# Flyback_Controller.net
KiCad netlist of a schematic drawn in Altium Designer
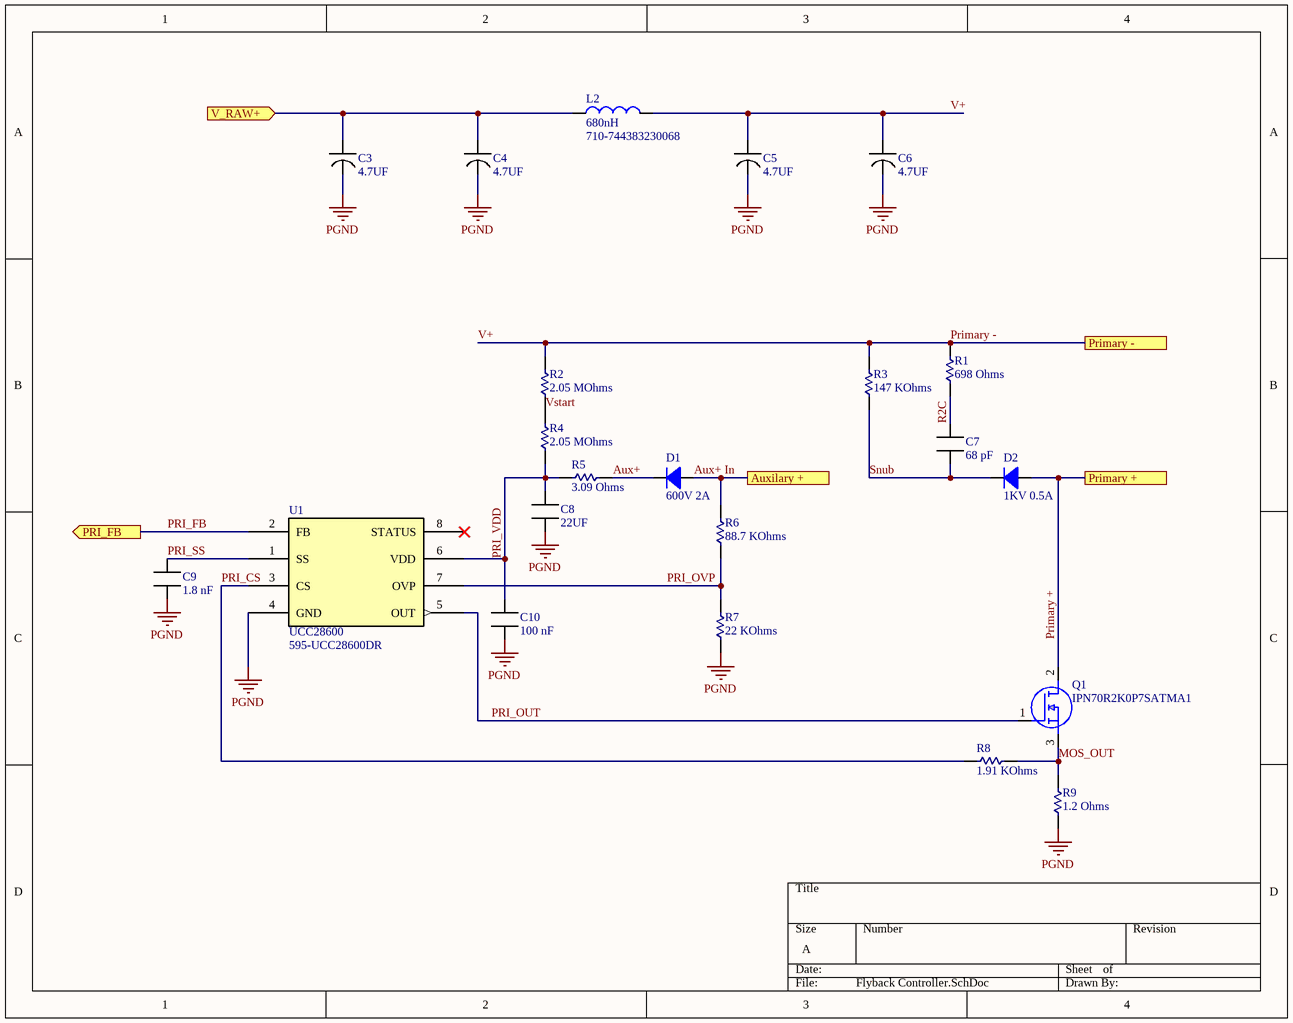
[diagram p0: Flyback Controller.SchDoc]

(export (version "E")
  (design (tool "Eeschema 10.0.6"))
  (components
    (comp (ref "C3")
      (value "4.7UF")
      (footprint "Alum Radial Cap 5mm")
      (description "Aluminum Electrolytic Capacitors - Radial Leaded 400V 4.7uF 20% 1000Hrs")
      (libsource (lib "SMPS Schlib") (part "ESE475M400AH9AA"))
    )
    (comp (ref "C4")
      (value "4.7UF")
      (footprint "Alum Radial Cap 5mm")
      (description "Aluminum Electrolytic Capacitors - Radial Leaded 400V 4.7uF 20% 1000Hrs")
      (libsource (lib "SMPS Schlib") (part "ESE475M400AH9AA"))
    )
    (comp (ref "C5")
      (value "4.7UF")
      (footprint "Alum Radial Cap 5mm")
      (description "Aluminum Electrolytic Capacitors - Radial Leaded 400V 4.7uF 20% 1000Hrs")
      (libsource (lib "SMPS Schlib") (part "ESE475M400AH9AA"))
    )
    (comp (ref "C6")
      (value "4.7UF")
      (footprint "Alum Radial Cap 5mm")
      (description "Aluminum Electrolytic Capacitors - Radial Leaded 400V 4.7uF 20% 1000Hrs")
      (libsource (lib "SMPS Schlib") (part "ESE475M400AH9AA"))
    )
    (comp (ref "C7")
      (value "68 pF")
      (footprint "Cap 1206")
      (description "Multilayer Ceramic Capacitors MLCC - SMD/SMT 1k V 68 pF C0G 1206 5%")
      (libsource (lib "SMPS Schlib") (part "CC1206JKNPOCBN680"))
    )
    (comp (ref "C8")
      (value "22UF")
      (footprint "Res 0805")
      (description "Multilayer Ceramic Capacitors MLCC - SMD/SMT 22uF+/-20% 25V X5R 2 0805")
      (libsource (lib "SMPS Schlib") (part "CL21A226MAYNNNE"))
    )
    (comp (ref "C9")
      (value "1.8 nF")
      (footprint "Cap 0603")
      (description "Multilayer Ceramic Capacitors MLCC - SMD/SMT 0603 1800pF 50volts X7R 10%")
      (libsource (lib "SMPS Schlib") (part "VJ0603Y182KXACW1BC"))
    )
    (comp (ref "C10")
      (value "100 nF")
      (footprint "Cap 1206")
      (description "Multilayer Ceramic Capacitors MLCC - SMD/SMT CGA 1206 450V 0.1uF X7T 20% AEC-Q200")
      (libsource (lib "SMPS Schlib") (part "CGA5L4X7T2W104M160AA"))
    )
    (comp (ref "D1")
      (value "600V 2A")
      (footprint "FLAT_SMT")
      (description "Diodes - General Purpose, Power, Switching 600V 2A M-FLAT")
      (libsource (lib "SMPS Schlib") (part "CMF01(TE12L,Q,M)"))
    )
    (comp (ref "D2")
      (value "1KV 0.5A")
      (footprint "FLAT_SMT")
      (description "Rectifiers Super Fast Diode 1000V 0.5A 100ns")
      (libsource (lib "SMPS Schlib") (part "CMF05(TE12L,Q,M)"))
    )
    (comp (ref "L2")
      (value "680nH")
      (footprint "IND 1008")
      (description "Power Inductors - Leaded WE-MAPI 680nH 3.1A DCR=60mOhms AECQ200")
      (fields (field (name "SUPPLIER PART NUMBER 1") "710-744383230068"))
      (libsource (lib "SMPS Schlib") (part "744383230068"))
    )
    (comp (ref "Q1")
      (value "IPN70R2K0P7SATMA1")
      (footprint "SOT-223-3")
      (description "MOSFET CONSUMER 700V 3A 1.64Ohms")
      (libsource (lib "SMPS Schlib") (part "IPN70R2K0P7SATMA1"))
    )
    (comp (ref "R1")
      (value "698 Ohms")
      (footprint "Res 0805")
      (description "Thick Film Resistors - SMD 698 Ohms 125 mW 0805 1%")
      (libsource (lib "SMPS Schlib") (part "RC0805FR-07698RL"))
    )
    (comp (ref "R2")
      (value "2.05 MOhms")
      (footprint "RES 1206")
      (description "Thick Film Resistors - SMD 2.05 MOhms 250 mW 1206 1%")
      (libsource (lib "SMPS Schlib") (part "RC1206FR-072M05L"))
    )
    (comp (ref "R3")
      (value "147 KOhms")
      (footprint "Res 0805")
      (description "Thick Film Resistors - SMD 0805 147Kohms 0.5W 1% AEC-Q200")
      (libsource (lib "SMPS Schlib") (part "ERJ-P06F1473V"))
    )
    (comp (ref "R4")
      (value "2.05 MOhms")
      (footprint "RES 1206")
      (description "Thick Film Resistors - SMD 2.05 MOhms 250 mW 1206 1%")
      (libsource (lib "SMPS Schlib") (part "RC1206FR-072M05L"))
    )
    (comp (ref "R5")
      (value "3.09 Ohms")
      (footprint "Res 0805")
      (description "Thick Film Resistors - SMD 3.09Ohms 1/8W 0805 1%")
      (libsource (lib "SMPS Schlib") (part "RC0805FR-073R09L"))
    )
    (comp (ref "R6")
      (value "88.7 KOhms")
      (footprint "Res 0805")
      (description "Thin Film Resistors - SMD 0805 88.7Kohm 0.1% 25ppm")
      (libsource (lib "SMPS Schlib") (part "ERA-6AEB8872V"))
    )
    (comp (ref "R7")
      (value "22 KOhms")
      (footprint "Res 0805")
      (description "Thin Film Resistors - SMD 1/8W 22K ohm .1% 25ppm")
      (libsource (lib "SMPS Schlib") (part "RT0805BRD0722KL"))
    )
    (comp (ref "R8")
      (value "1.91 KOhms")
      (footprint "Res 0805")
      (description "Thick Film Resistors - SMD 1.91K 1%")
      (libsource (lib "SMPS Schlib") (part "CR0805-FX-1911ELF"))
    )
    (comp (ref "R9")
      (value "1.2 Ohms")
      (footprint "RES 1206")
      (description "Thick Film Resistors - SMD 1.2Ohms 1/4W 1206 1% AEC-Q200 Standard Power Version")
      (libsource (lib "SMPS Schlib") (part "AC1206FR-071R2L"))
    )
    (comp (ref "U1")
      (value "UCC28600")
      (footprint "UCC28600")
      (description "AC/DC Converters Quasi Res Flyback Green Mode Cntrlr")
      (fields (field (name "SUPPLIER PART NUMBER 1") "595-UCC28600DR"))
      (libsource (lib "SMPS Schlib") (part "UCC28600DR"))
    )
  )
  (nets
    (net (code "1") (name "/Aux+") (class "Default")
      (node (ref "D1") (pin "2") (pinfunction "2_2") (pintype "passive"))
      (node (ref "R5") (pin "2") (pinfunction "B_2") (pintype "passive"))
    )
    (net (code "2") (name "/Aux+ In") (class "Default")
      (node (ref "D1") (pin "1") (pinfunction "1_1") (pintype "passive"))
      (node (ref "R6") (pin "2") (pinfunction "B_2") (pintype "passive"))
    )
    (net (code "3") (name "/MOS_OUT") (class "Default")
      (node (ref "Q1") (pin "3") (pinfunction "S_3") (pintype "passive"))
      (node (ref "R8") (pin "2") (pinfunction "B_2") (pintype "passive"))
      (node (ref "R9") (pin "2") (pinfunction "B_2") (pintype "passive"))
    )
    (net (code "4") (name "/PRI_CS") (class "Default")
      (node (ref "R8") (pin "1") (pinfunction "A_1") (pintype "passive"))
      (node (ref "U1") (pin "3") (pinfunction "CS_3") (pintype "passive"))
    )
    (net (code "5") (name "/PRI_FB") (class "Default")
      (node (ref "U1") (pin "2") (pinfunction "FB_2") (pintype "passive"))
    )
    (net (code "6") (name "/PRI_OUT") (class "Default")
      (node (ref "Q1") (pin "1") (pinfunction "G_1") (pintype "passive"))
      (node (ref "U1") (pin "5") (pinfunction "OUT_5") (pintype "output"))
    )
    (net (code "7") (name "/PRI_OVP") (class "Default")
      (node (ref "R6") (pin "1") (pinfunction "A_1") (pintype "passive"))
      (node (ref "R7") (pin "2") (pinfunction "B_2") (pintype "passive"))
      (node (ref "U1") (pin "7") (pinfunction "OVP_7") (pintype "passive"))
    )
    (net (code "8") (name "/PRI_SS") (class "Default")
      (node (ref "C9") (pin "2") (pinfunction "2_2") (pintype "passive"))
      (node (ref "U1") (pin "1") (pinfunction "SS_1") (pintype "passive"))
    )
    (net (code "9") (name "/PRI_VDD") (class "Default")
      (node (ref "C10") (pin "2") (pinfunction "2_2") (pintype "passive"))
      (node (ref "C8") (pin "2") (pinfunction "2_2") (pintype "passive"))
      (node (ref "R4") (pin "1") (pinfunction "A_1") (pintype "passive"))
      (node (ref "R5") (pin "1") (pinfunction "A_1") (pintype "passive"))
      (node (ref "U1") (pin "6") (pinfunction "VDD_6") (pintype "power_in"))
    )
    (net (code "10") (name "/Primary +") (class "Default")
      (node (ref "D2") (pin "1") (pinfunction "1_1") (pintype "passive"))
      (node (ref "Q1") (pin "2") (pinfunction "D_2") (pintype "passive"))
    )
    (net (code "11") (name "/Primary -") (class "Default")
      (node (ref "C5") (pin "1") (pinfunction "1_1") (pintype "passive"))
      (node (ref "C6") (pin "1") (pinfunction "1_1") (pintype "passive"))
      (node (ref "L2") (pin "2") (pinfunction "2_2") (pintype "passive"))
      (node (ref "R1") (pin "2") (pinfunction "B_2") (pintype "passive"))
      (node (ref "R2") (pin "2") (pinfunction "B_2") (pintype "passive"))
      (node (ref "R3") (pin "2") (pinfunction "B_2") (pintype "passive"))
    )
    (net (code "12") (name "/R2C") (class "Default")
      (node (ref "C7") (pin "2") (pinfunction "2_2") (pintype "passive"))
      (node (ref "R1") (pin "1") (pinfunction "A_1") (pintype "passive"))
    )
    (net (code "13") (name "/Snub") (class "Default")
      (node (ref "C7") (pin "1") (pinfunction "1_1") (pintype "passive"))
      (node (ref "D2") (pin "2") (pinfunction "2_2") (pintype "passive"))
      (node (ref "R3") (pin "1") (pinfunction "A_1") (pintype "passive"))
    )
    (net (code "14") (name "/V_RAW+") (class "Default")
      (node (ref "C3") (pin "1") (pinfunction "1_1") (pintype "passive"))
      (node (ref "C4") (pin "1") (pinfunction "1_1") (pintype "passive"))
      (node (ref "L2") (pin "1") (pinfunction "1_1") (pintype "passive"))
    )
    (net (code "15") (name "/Vstart") (class "Default")
      (node (ref "R2") (pin "1") (pinfunction "A_1") (pintype "passive"))
      (node (ref "R4") (pin "2") (pinfunction "B_2") (pintype "passive"))
    )
    (net (code "16") (name "PGND") (class "Default")
      (node (ref "C10") (pin "1") (pinfunction "1_1") (pintype "passive"))
      (node (ref "C3") (pin "2") (pinfunction "2_2") (pintype "passive"))
      (node (ref "C4") (pin "2") (pinfunction "2_2") (pintype "passive"))
      (node (ref "C5") (pin "2") (pinfunction "2_2") (pintype "passive"))
      (node (ref "C6") (pin "2") (pinfunction "2_2") (pintype "passive"))
      (node (ref "C8") (pin "1") (pinfunction "1_1") (pintype "passive"))
      (node (ref "C9") (pin "1") (pinfunction "1_1") (pintype "passive"))
      (node (ref "R7") (pin "1") (pinfunction "A_1") (pintype "passive"))
      (node (ref "R9") (pin "1") (pinfunction "A_1") (pintype "passive"))
      (node (ref "U1") (pin "4") (pinfunction "GND_4") (pintype "power_in"))
    )
    (net (code "17") (name "unconnected-(U1-STATUS-Pad8)") (class "Default")
      (node (ref "U1") (pin "8") (pinfunction "STATUS_8") (pintype "passive+no_connect"))
    )
  )
)
